# LED_Light_Schematic.net
KiCad netlist of a schematic drawn in Altium Designer
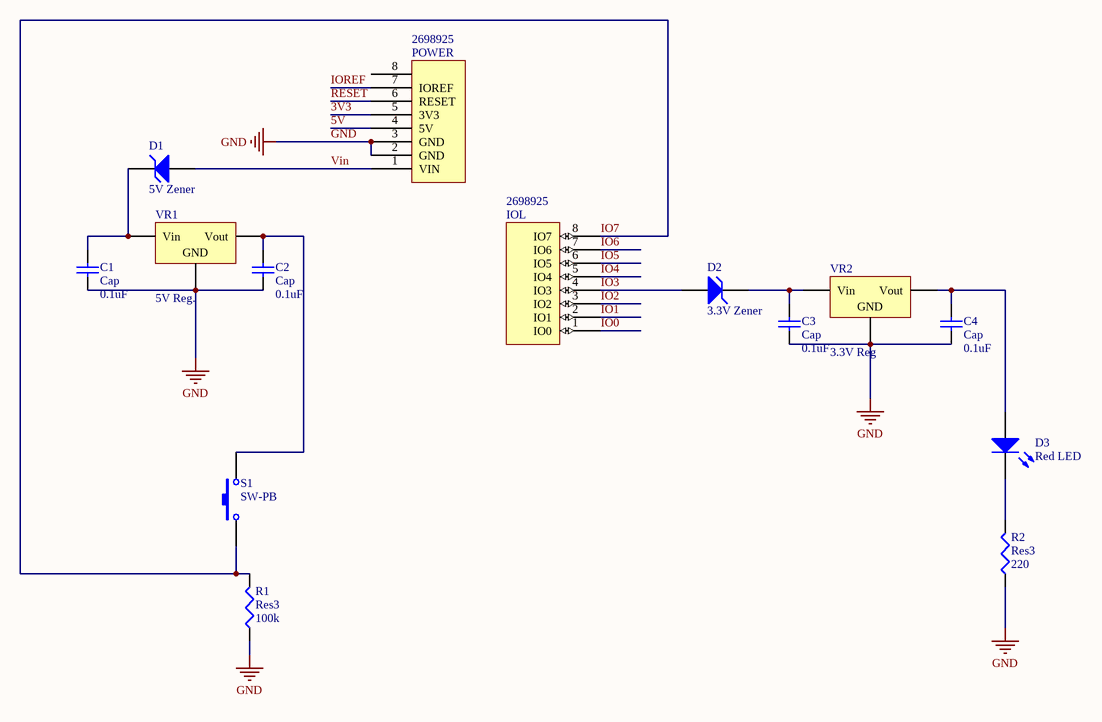
[diagram p0: LED Light Schematic.SchDoc]

(export (version "E")
  (design (tool "Eeschema 10.0.6"))
  (components
    (comp (ref "C1")
      (value "Cap")
      (footprint "RAD-0.3")
      (description "Capacitor")
      (fields (field (name "ALTIUM_VALUE") "0.1uF") (field (name "PUBLISHER") "Altium Limited"))
      (libsource (lib "Miscellaneous Devices") (part "Cap"))
    )
    (comp (ref "C2")
      (value "Cap")
      (footprint "RAD-0.3")
      (description "Capacitor")
      (fields (field (name "ALTIUM_VALUE") "0.1uF") (field (name "PUBLISHER") "Altium Limited"))
      (libsource (lib "Miscellaneous Devices") (part "Cap"))
    )
    (comp (ref "C3")
      (value "Cap")
      (footprint "RAD-0.3")
      (description "Capacitor")
      (fields (field (name "ALTIUM_VALUE") "0.1uF") (field (name "PUBLISHER") "Altium Limited"))
      (libsource (lib "Miscellaneous Devices") (part "Cap"))
    )
    (comp (ref "C4")
      (value "Cap")
      (footprint "RAD-0.3")
      (description "Capacitor")
      (fields (field (name "ALTIUM_VALUE") "0.1uF") (field (name "PUBLISHER") "Altium Limited"))
      (libsource (lib "Miscellaneous Devices") (part "Cap"))
    )
    (comp (ref "D1")
      (value "5V Zener")
      (footprint "DIODE-0.7")
      (description "Zener Diode")
      (fields (field (name "PUBLISHER") "Altium Limited"))
      (libsource (lib "Miscellaneous Devices") (part "D Zener"))
    )
    (comp (ref "D2")
      (value "3.3V Zener")
      (footprint "DIODE-0.7")
      (description "Zener Diode")
      (fields (field (name "PUBLISHER") "Altium Limited"))
      (libsource (lib "Miscellaneous Devices") (part "D Zener"))
    )
    (comp (ref "D3")
      (value "Red LED")
      (footprint "3.2X1.6X1.1")
      (description "Typical RED, GREEN, YELLOW, AMBER GaAs LED")
      (fields (field (name "PUBLISHER") "Altium Limited"))
      (libsource (lib "Miscellaneous Devices") (part "LED2"))
    )
    (comp (ref "IOL")
      (value "IOL")
      (footprint "Header 8x1 8.5mm")
      (fields (field (name "SUPPLIER PART NUMBER 4") "2698925"))
      (libsource (lib "Header") (part "IOL"))
    )
    (comp (ref "POWER")
      (value "POWER_UNO")
      (footprint "Header 8x1 8.5mm")
      (fields (field (name "SUPPLIER PART NUMBER 4") "2698925"))
      (libsource (lib "Header") (part "POWER_UNO"))
    )
    (comp (ref "R1")
      (value "Res3")
      (footprint "J1-0603")
      (description "Resistor")
      (fields (field (name "ALTIUM_VALUE") "100k") (field (name "PUBLISHER") "Altium Limited"))
      (libsource (lib "Miscellaneous Devices") (part "Res3"))
    )
    (comp (ref "R2")
      (value "Res3")
      (footprint "J1-0603")
      (description "Resistor")
      (fields (field (name "ALTIUM_VALUE") "220") (field (name "PUBLISHER") "Altium Limited"))
      (libsource (lib "Miscellaneous Devices") (part "Res3"))
    )
    (comp (ref "S1")
      (value "SW-PB")
      (footprint "SPST-2")
      (description "Switch")
      (fields (field (name "PUBLISHER") "Altium Limited"))
      (libsource (lib "Miscellaneous Devices") (part "SW-PB"))
    )
    (comp (ref "VR1")
      (value "5V Reg.")
      (footprint "D2PAK_M")
      (description "Voltage Regulator")
      (fields (field (name "PUBLISHER") "Altium Limited"))
      (libsource (lib "Miscellaneous Devices") (part "Volt Reg"))
    )
    (comp (ref "VR2")
      (value "3.3V Reg")
      (footprint "D2PAK_N")
      (description "Voltage Regulator")
      (fields (field (name "PUBLISHER") "Altium Limited"))
      (libsource (lib "Miscellaneous Devices") (part "Volt Reg"))
    )
  )
  (nets
    (net (code "1") (name "/3V3") (class "Default")
      (node (ref "POWER") (pin "5") (pinfunction "3V3_5") (pintype "power_in"))
    )
    (net (code "2") (name "/5V") (class "Default")
      (node (ref "POWER") (pin "4") (pinfunction "5V_4") (pintype "power_in"))
    )
    (net (code "4") (name "/IO0") (class "Default")
      (node (ref "IOL") (pin "1") (pinfunction "IO0_1") (pintype "bidirectional"))
    )
    (net (code "5") (name "/IO1") (class "Default")
      (node (ref "IOL") (pin "2") (pinfunction "IO1_2") (pintype "bidirectional"))
    )
    (net (code "6") (name "/IO2") (class "Default")
      (node (ref "IOL") (pin "3") (pinfunction "IO2_3") (pintype "bidirectional"))
    )
    (net (code "7") (name "/IO3") (class "Default")
      (node (ref "D2") (pin "1") (pinfunction "A_1") (pintype "passive"))
      (node (ref "IOL") (pin "4") (pinfunction "IO3_4") (pintype "bidirectional"))
    )
    (net (code "8") (name "/IO4") (class "Default")
      (node (ref "IOL") (pin "5") (pinfunction "IO4_5") (pintype "bidirectional"))
    )
    (net (code "9") (name "/IO5") (class "Default")
      (node (ref "IOL") (pin "6") (pinfunction "IO5_6") (pintype "bidirectional"))
    )
    (net (code "10") (name "/IO6") (class "Default")
      (node (ref "IOL") (pin "7") (pinfunction "IO6_7") (pintype "bidirectional"))
    )
    (net (code "11") (name "/IO7") (class "Default")
      (node (ref "IOL") (pin "8") (pinfunction "IO7_8") (pintype "bidirectional"))
      (node (ref "R1") (pin "2") (pinfunction "2_2") (pintype "passive"))
      (node (ref "S1") (pin "1") (pinfunction "1_1") (pintype "passive"))
    )
    (net (code "12") (name "/IOREF") (class "Default")
      (node (ref "POWER") (pin "7") (pinfunction "IOREF_7") (pintype "power_in"))
    )
    (net (code "13") (name "/RESET") (class "Default")
      (node (ref "POWER") (pin "6") (pinfunction "RESET_6") (pintype "passive"))
    )
    (net (code "14") (name "/Vin") (class "Default")
      (node (ref "D1") (pin "1") (pinfunction "A_1") (pintype "passive"))
      (node (ref "POWER") (pin "1") (pinfunction "VIN_1") (pintype "power_in"))
    )
    (net (code "15") (name "GND") (class "Default")
      (node (ref "C1") (pin "1") (pinfunction "1_1") (pintype "passive"))
      (node (ref "C2") (pin "1") (pinfunction "1_1") (pintype "passive"))
      (node (ref "C3") (pin "1") (pinfunction "1_1") (pintype "passive"))
      (node (ref "C4") (pin "1") (pinfunction "1_1") (pintype "passive"))
      (node (ref "POWER") (pin "2") (pinfunction "GND_2") (pintype "power_in"))
      (node (ref "POWER") (pin "3") (pinfunction "GND_3") (pintype "power_in"))
      (node (ref "R1") (pin "1") (pinfunction "1_1") (pintype "passive"))
      (node (ref "R2") (pin "1") (pinfunction "1_1") (pintype "passive"))
      (node (ref "VR1") (pin "2") (pinfunction "GND_2") (pintype "passive"))
      (node (ref "VR2") (pin "2") (pinfunction "GND_2") (pintype "passive"))
    )
    (net (code "16") (name "Net-(D1-K)") (class "Default")
      (node (ref "C1") (pin "2") (pinfunction "2_2") (pintype "passive"))
      (node (ref "D1") (pin "2") (pinfunction "K_2") (pintype "passive"))
      (node (ref "VR1") (pin "1") (pinfunction "Vin_1") (pintype "passive"))
    )
    (net (code "17") (name "Net-(D2-K)") (class "Default")
      (node (ref "C3") (pin "2") (pinfunction "2_2") (pintype "passive"))
      (node (ref "D2") (pin "2") (pinfunction "K_2") (pintype "passive"))
      (node (ref "VR2") (pin "1") (pinfunction "Vin_1") (pintype "passive"))
    )
    (net (code "18") (name "Net-(D3-A)") (class "Default")
      (node (ref "C4") (pin "2") (pinfunction "2_2") (pintype "passive"))
      (node (ref "D3") (pin "1") (pinfunction "A_1") (pintype "passive"))
      (node (ref "VR2") (pin "3") (pinfunction "Vout_3") (pintype "passive"))
    )
    (net (code "19") (name "Net-(D3-K)") (class "Default")
      (node (ref "D3") (pin "2") (pinfunction "K_2") (pintype "passive"))
      (node (ref "R2") (pin "2") (pinfunction "2_2") (pintype "passive"))
    )
    (net (code "20") (name "Net-(VR1-Vout)") (class "Default")
      (node (ref "C2") (pin "2") (pinfunction "2_2") (pintype "passive"))
      (node (ref "S1") (pin "2") (pinfunction "2_2") (pintype "passive"))
      (node (ref "VR1") (pin "3") (pinfunction "Vout_3") (pintype "passive"))
    )
    (net (code "21") (name "unconnected-(POWER-Pad8)") (class "Default")
      (node (ref "POWER") (pin "8") (pintype "passive"))
    )
  )
)
